# Connectors.net
KiCad netlist of a schematic drawn in Altium Designer
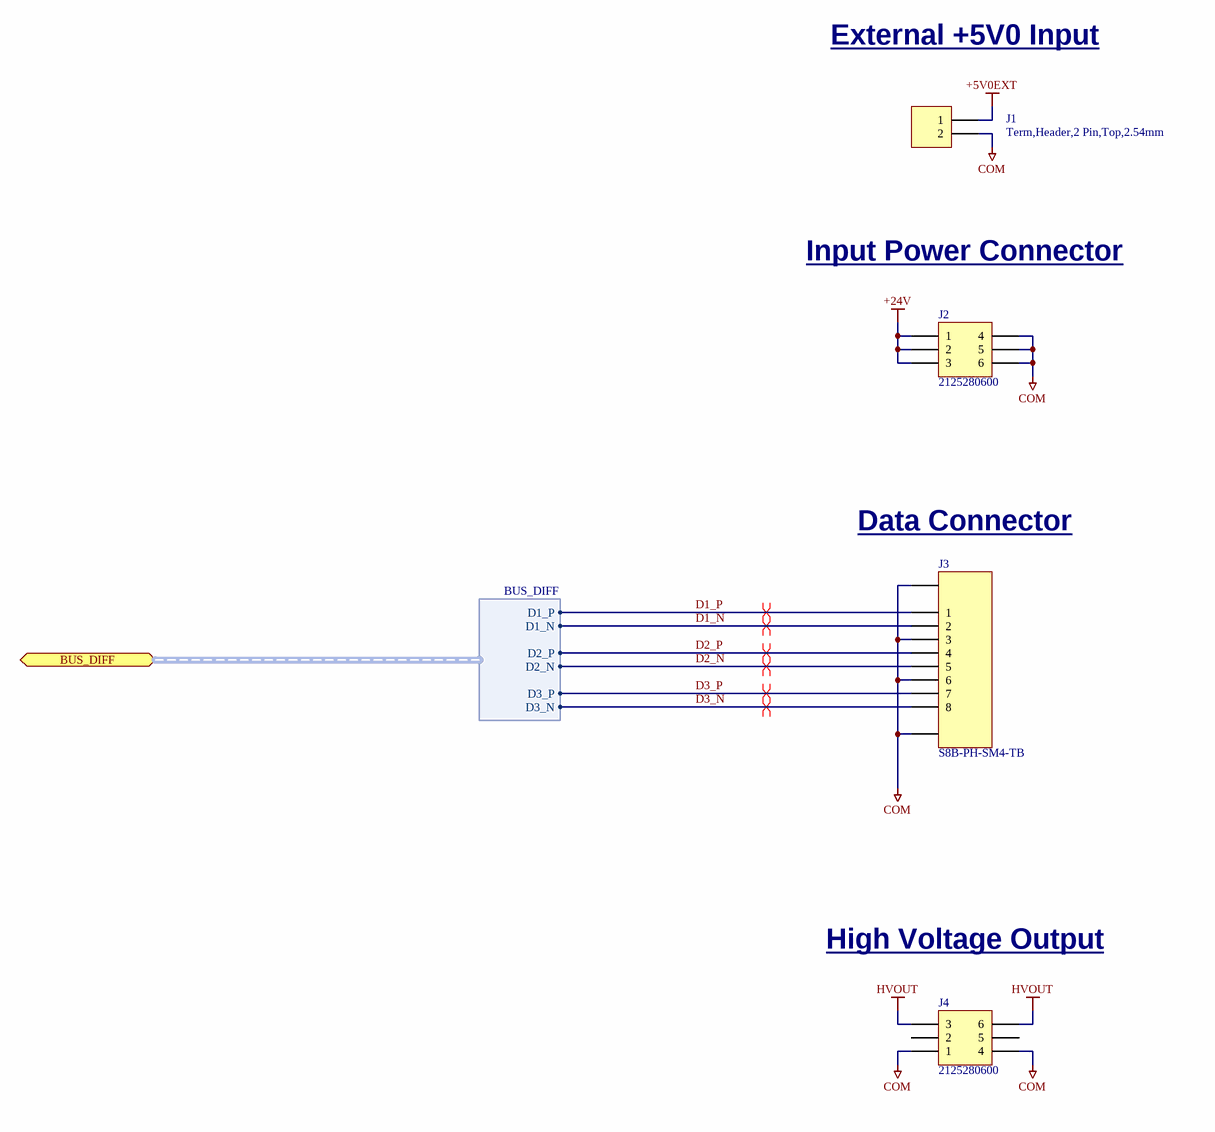
[diagram p0: Connectors.SchDoc]

(export (version "E")
  (design (tool "Eeschema 10.0.6"))
  (components
    (comp (ref "J1")
      (value "Term,Header,2 Pin,Top,2.54mm")
      (footprint "WURTH_61300211121")
      (description "Connector Header Through Hole 2 position 0.100\" (2.54mm)")
      (fields
        (field (name "MANUFACTURER 1 PART NUMBER") "61300211121")
        (field (name "VENDOR 1 PART NUMBER") "732-5315-ND")
        (field (name "CREATEDBY") "Judd Foster")
      )
      (libsource (lib "Component Library") (part "Term,Header,2 Pin,Top,2.54mm"))
    )
    (comp (ref "J2")
      (value "2125280600")
      (footprint "MOLEX_2125280600")
      (description "Connector Header Through Hole, Right Angle 6 position 0.118\" (3.00mm)")
      (fields
        (field (name "VENDOR 1 PART NUMBER") "900-2125280600-ND")
        (field (name "CREATEDBY") "Judd Foster")
      )
      (libsource (lib "Component Library") (part "Conn,Micro-Fit,Hdr,6Pos,RA,Thru"))
    )
    (comp (ref "J3")
      (value "S8B-PH-SM4-TB")
      (footprint "JST_S8B-PH-SM4-TB")
      (description "Connector Header Surface Mount, Right Angle 8 position 0.079\" (2.00mm)")
      (fields
        (field (name "VENDOR 1 PART NUMBER") "455-S8B-PH-SM4-TBCT-ND")
        (field (name "CREATEDBY") "Judd Foster")
      )
      (libsource (lib "Component Library") (part "CONN,JST,8 Pin,2mm,RA,SMD"))
    )
    (comp (ref "J4")
      (value "2125280600")
      (footprint "MOLEX_2125280600")
      (description "Connector Header Through Hole, Right Angle 6 position 0.118\" (3.00mm)")
      (fields
        (field (name "VENDOR 1 PART NUMBER") "900-2125280600-ND")
        (field (name "CREATEDBY") "Judd Foster")
      )
      (libsource (lib "") (part "Conn,Micro-Fit,Hdr,6Pos,RA,Thru_1"))
    )
  )
  (nets
    (net (code "2") (name "+5V0EXT") (class "Default")
      (node (ref "J1") (pin "1") (pinfunction "1_1") (pintype "passive"))
    )
    (net (code "3") (name "+24V") (class "Default")
      (node (ref "J2") (pin "1") (pinfunction "1_1") (pintype "passive"))
      (node (ref "J2") (pin "2") (pinfunction "2_2") (pintype "passive"))
      (node (ref "J2") (pin "3") (pinfunction "3_3") (pintype "passive"))
    )
    (net (code "4") (name "/D1_N") (class "Default")
      (node (ref "J3") (pin "2") (pinfunction "2_2") (pintype "passive"))
    )
    (net (code "5") (name "/D1_P") (class "Default")
      (node (ref "J3") (pin "1") (pinfunction "1_1") (pintype "passive"))
    )
    (net (code "6") (name "/D2_N") (class "Default")
      (node (ref "J3") (pin "5") (pinfunction "5_5") (pintype "passive"))
    )
    (net (code "7") (name "/D2_P") (class "Default")
      (node (ref "J3") (pin "4") (pinfunction "4_4") (pintype "passive"))
    )
    (net (code "8") (name "/D3_N") (class "Default")
      (node (ref "J3") (pin "8") (pinfunction "8_8") (pintype "passive"))
    )
    (net (code "9") (name "/D3_P") (class "Default")
      (node (ref "J3") (pin "7") (pinfunction "7_7") (pintype "passive"))
    )
    (net (code "11") (name "COM") (class "Default")
      (node (ref "J1") (pin "2") (pinfunction "2_2") (pintype "passive"))
      (node (ref "J2") (pin "4") (pinfunction "4_4") (pintype "passive"))
      (node (ref "J2") (pin "5") (pinfunction "5_5") (pintype "passive"))
      (node (ref "J2") (pin "6") (pinfunction "6_6") (pintype "passive"))
      (node (ref "J3") (pin "0") (pintype "passive"))
      (node (ref "J3") (pin "3") (pinfunction "3_3") (pintype "passive"))
      (node (ref "J3") (pin "6") (pinfunction "6_6") (pintype "passive"))
      (node (ref "J4") (pin "1") (pinfunction "1_1") (pintype "passive"))
      (node (ref "J4") (pin "4") (pinfunction "4_4") (pintype "passive"))
    )
    (net (code "12") (name "HVOUT") (class "Default")
      (node (ref "J4") (pin "3") (pinfunction "3_3") (pintype "passive"))
      (node (ref "J4") (pin "6") (pinfunction "6_6") (pintype "passive"))
    )
    (net (code "13") (name "unconnected-(J4-Pad2)") (class "Default")
      (node (ref "J4") (pin "2") (pinfunction "2_2") (pintype "passive"))
    )
    (net (code "14") (name "unconnected-(J4-Pad5)") (class "Default")
      (node (ref "J4") (pin "5") (pinfunction "5_5") (pintype "passive"))
    )
  )
)
